# motor_module_dev.net
KiCad netlist of a schematic drawn in EAGLE
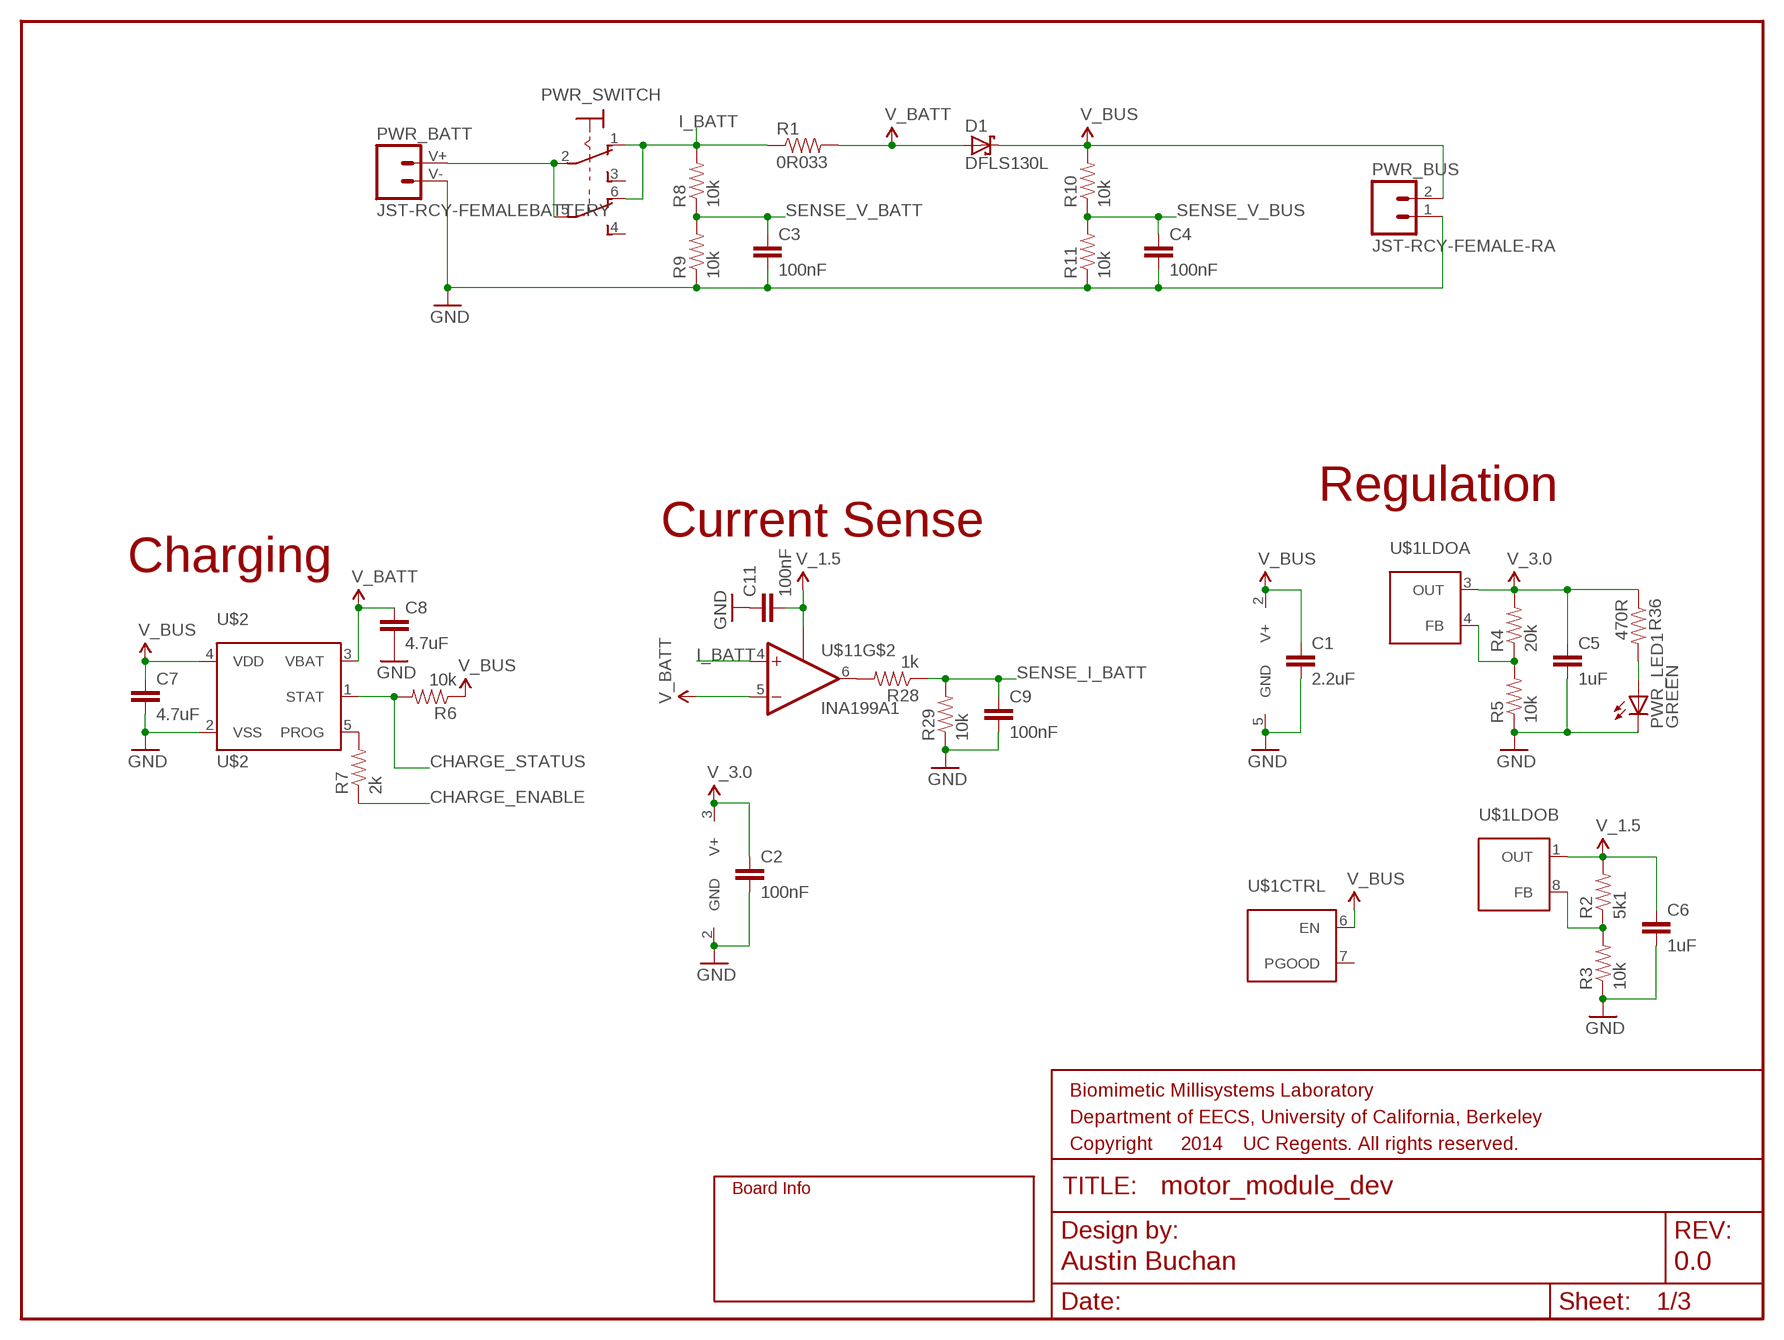
[diagram p0: schematic, sheet 1]
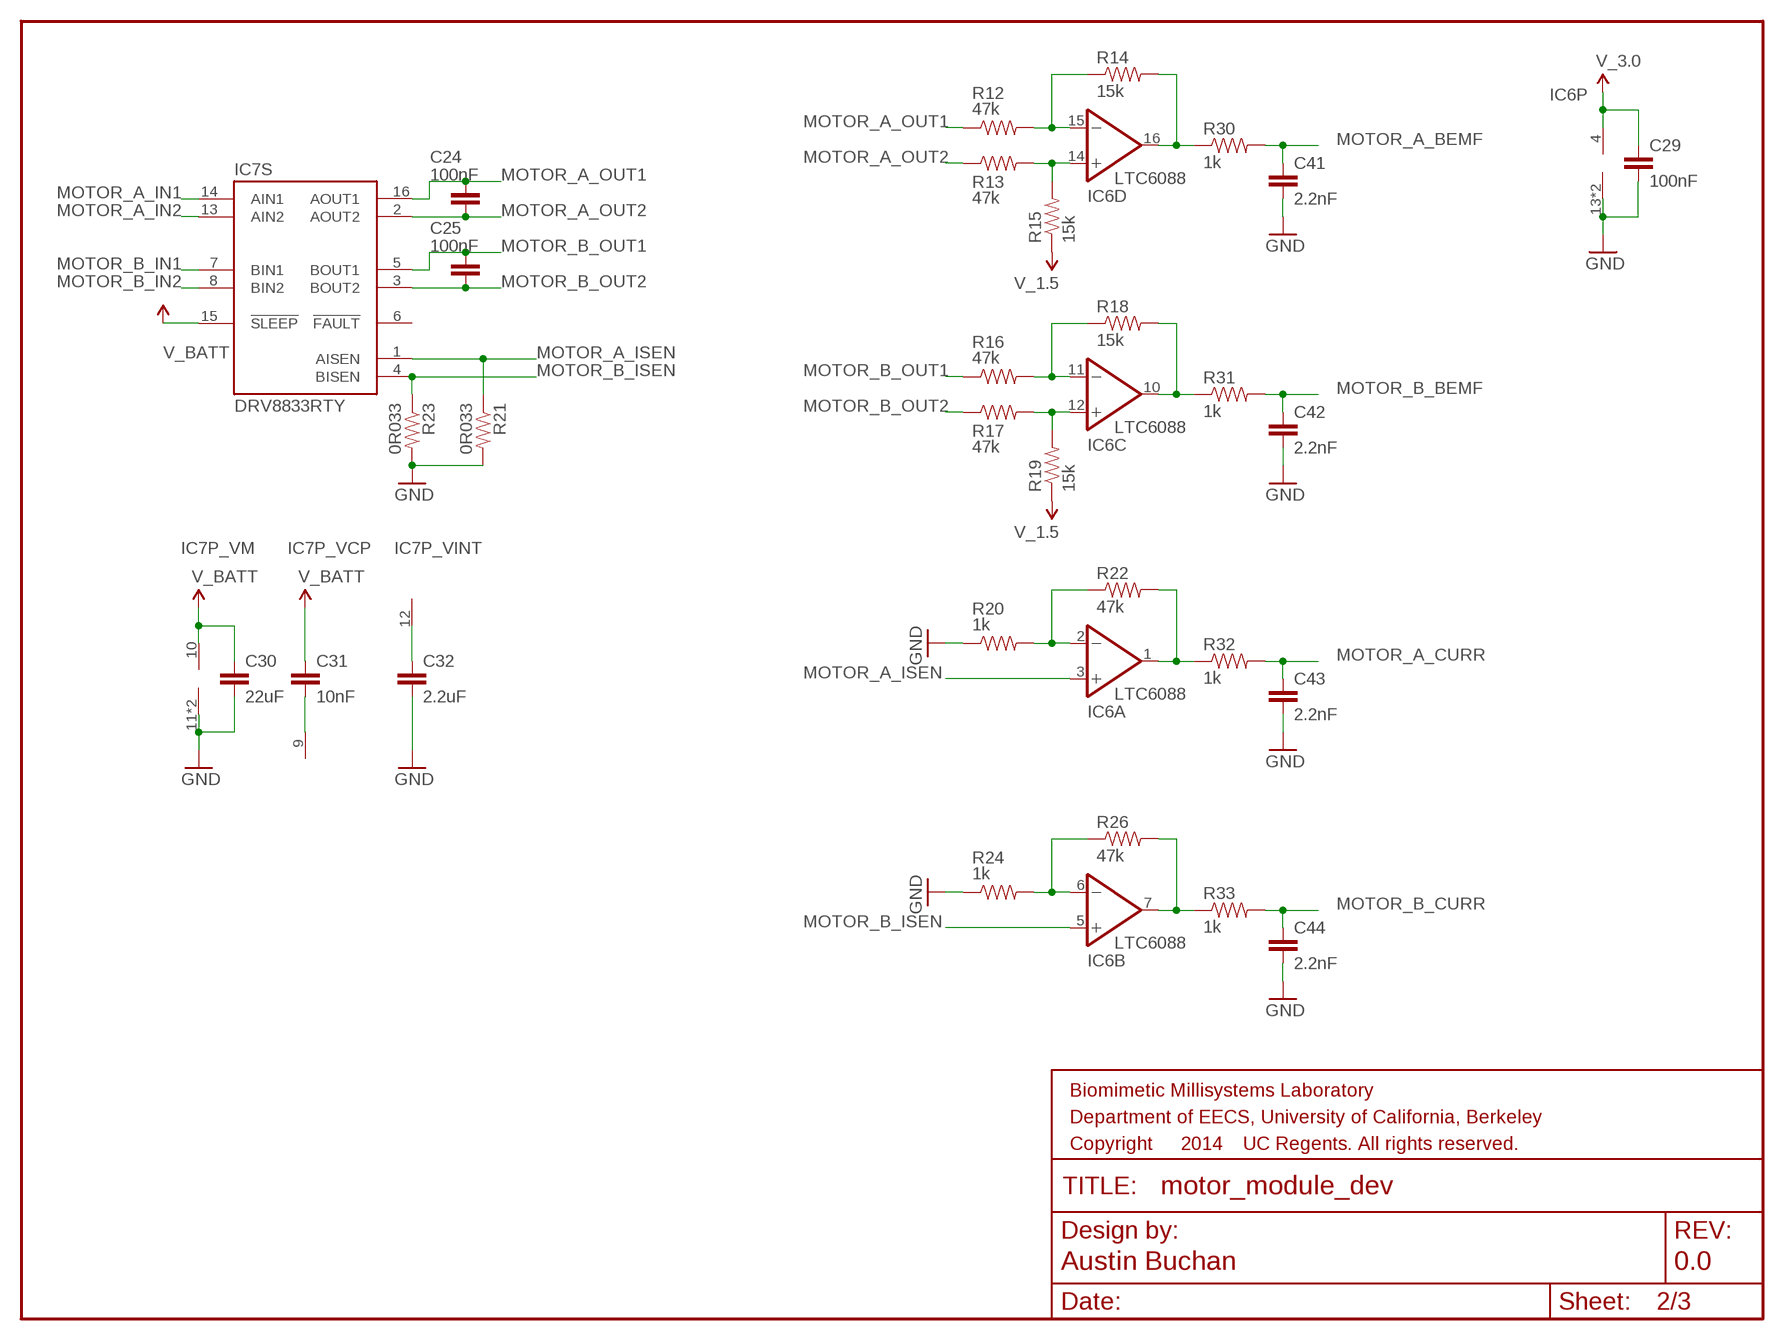
[diagram p1: schematic, sheet 2]
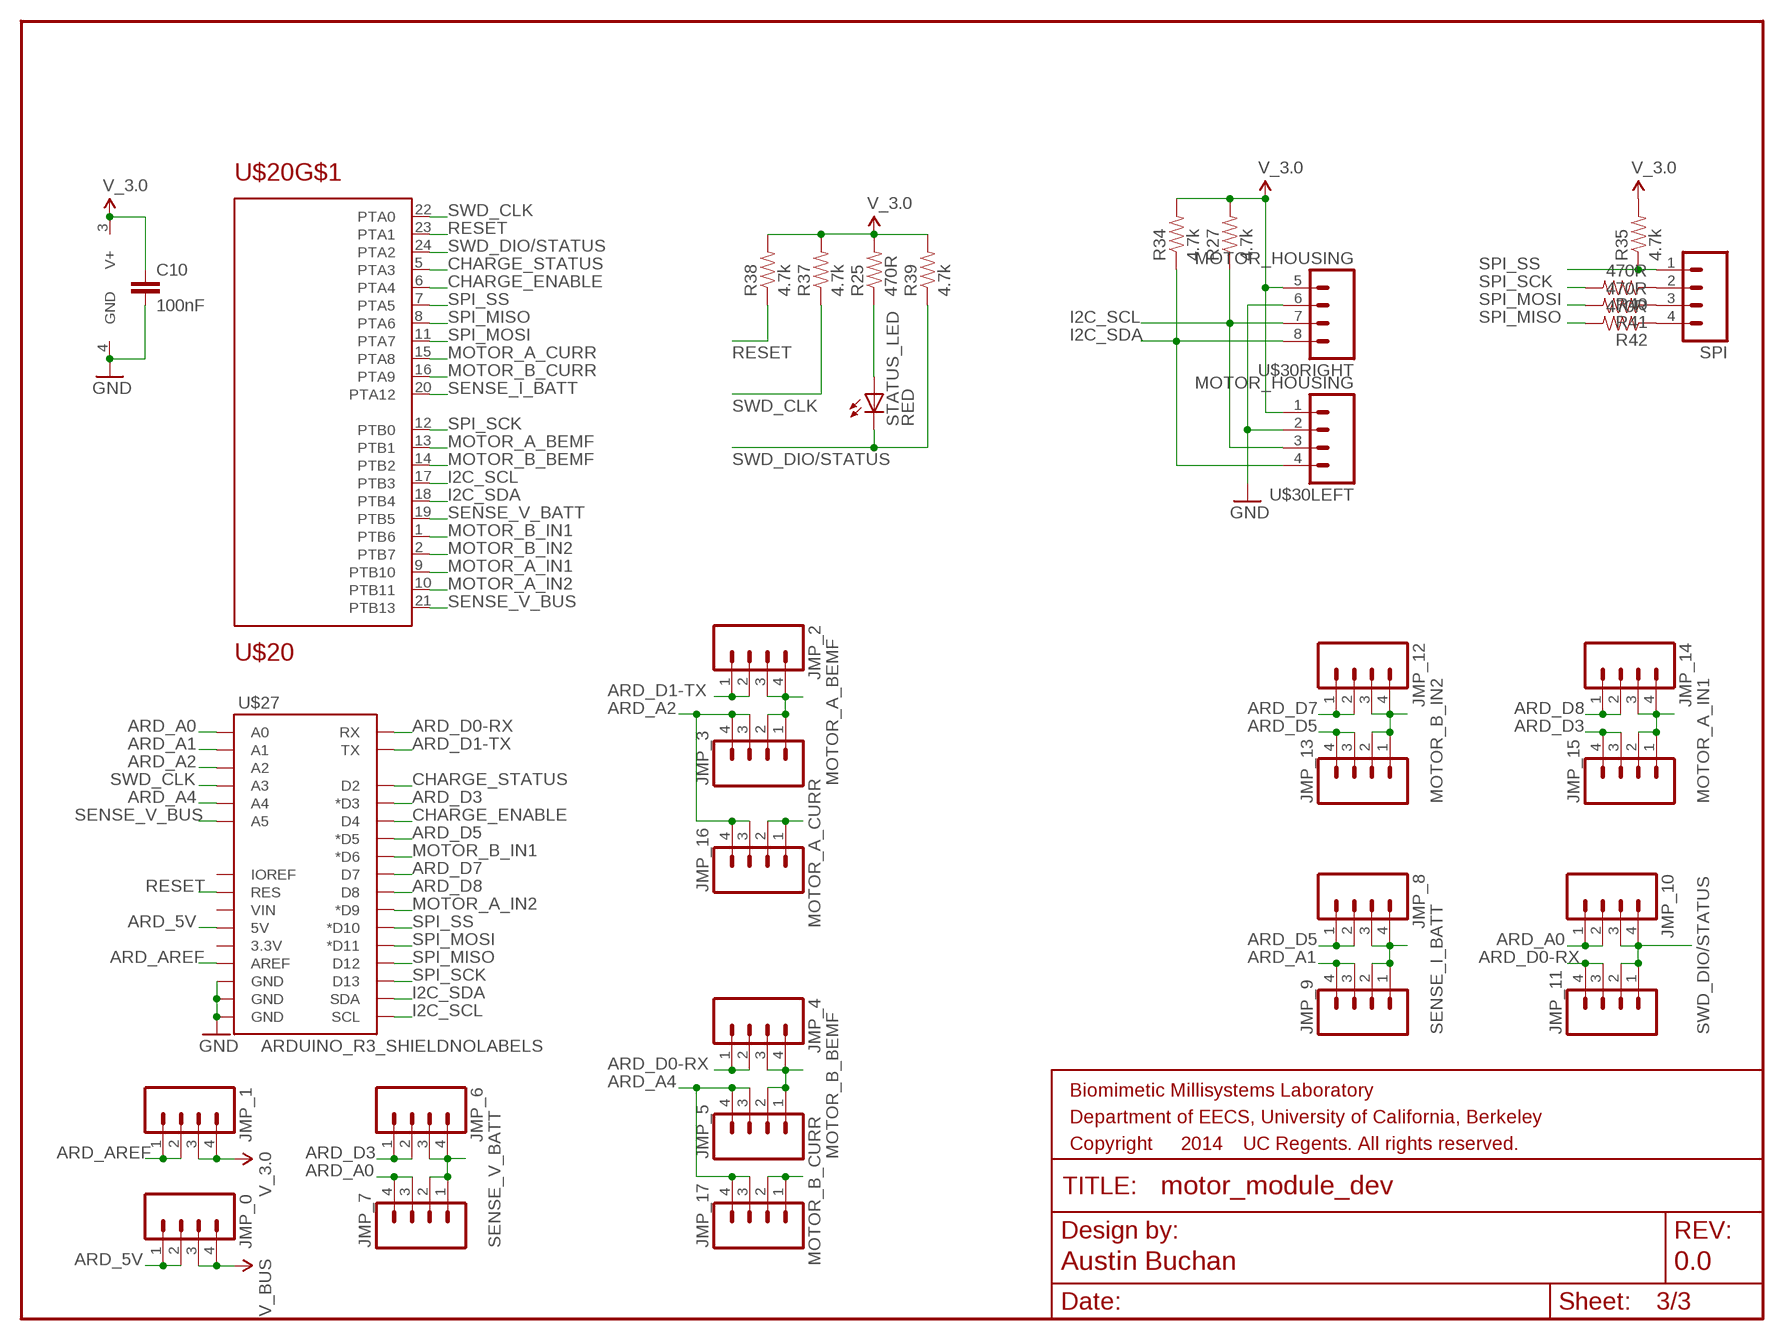
[diagram p2: schematic, sheet 3]

(export (version "E")
  (design (tool "Eeschema 10.0.6"))
  (components
    (comp (ref "C24")
      (value "100nF")
      (footprint "eagle-import:0402-CAP")
      (fields (field (name "VOLTAGE") "10V"))
      (libsource (lib "eagle-import") (part "CAP0402-CAP"))
    )
    (comp (ref "C25")
      (value "100nF")
      (footprint "eagle-import:0402-CAP")
      (fields (field (name "VOLTAGE") "10V"))
      (libsource (lib "eagle-import") (part "CAP0402-CAP"))
    )
    (comp (ref "C29")
      (value "100nF")
      (footprint "eagle-import:0402-CAP")
      (fields (field (name "VOLTAGE") "6.3V"))
      (libsource (lib "eagle-import") (part "CAP0402-CAP"))
    )
    (comp (ref "C30")
      (value "22uF")
      (footprint "eagle-import:0603-CAP")
      (fields (field (name "VOLTAGE") "10V"))
      (libsource (lib "eagle-import") (part "CAP0603-CAP"))
    )
    (comp (ref "C31")
      (value "10nF")
      (footprint "eagle-import:0402-CAP")
      (fields (field (name "VOLTAGE") "16V"))
      (libsource (lib "eagle-import") (part "CAP0402-CAP"))
    )
    (comp (ref "C32")
      (value "2.2uF")
      (footprint "eagle-import:0402-CAP")
      (fields (field (name "VOLTAGE") "6.3V"))
      (libsource (lib "eagle-import") (part "CAP0402-CAP"))
    )
    (comp (ref "C41")
      (value "2.2nF")
      (footprint "eagle-import:0402-CAP")
      (fields (field (name "VOLTAGE") "6.3V"))
      (libsource (lib "eagle-import") (part "CAP0402-CAP"))
    )
    (comp (ref "C42")
      (value "2.2nF")
      (footprint "eagle-import:0402-CAP")
      (fields (field (name "VOLTAGE") "6.3V"))
      (libsource (lib "eagle-import") (part "CAP0402-CAP"))
    )
    (comp (ref "C43")
      (value "2.2nF")
      (footprint "eagle-import:0402-CAP")
      (fields (field (name "VOLTAGE") "6.3V"))
      (libsource (lib "eagle-import") (part "CAP0402-CAP"))
    )
    (comp (ref "C44")
      (value "2.2nF")
      (footprint "eagle-import:0402-CAP")
      (fields (field (name "VOLTAGE") "6.3V"))
      (libsource (lib "eagle-import") (part "CAP0402-CAP"))
    )
    (comp (ref "IC6")
      (value "LTC6088")
      (footprint "eagle-import:DFN-16")
      (libsource (lib "eagle-import") (part "LTC6088"))
    )
    (comp (ref "IC7")
      (value "DRV8833RTY")
      (footprint "eagle-import:S-PWQFN-N16")
      (libsource (lib "eagle-import") (part "DRV8833RTY"))
    )
    (comp (ref "R12")
      (value "47k")
      (footprint "eagle-import:0402-RES")
      (fields (field (name "TOLERANCE") "1%"))
      (libsource (lib "eagle-import") (part "RESISTOR0402-RES"))
    )
    (comp (ref "R13")
      (value "47k")
      (footprint "eagle-import:0402-RES")
      (fields (field (name "TOLERANCE") "1%"))
      (libsource (lib "eagle-import") (part "RESISTOR0402-RES"))
    )
    (comp (ref "R14")
      (value "15k")
      (footprint "eagle-import:0402-RES")
      (fields (field (name "TOLERANCE") "1%"))
      (libsource (lib "eagle-import") (part "RESISTOR0402-RES"))
    )
    (comp (ref "R15")
      (value "15k")
      (footprint "eagle-import:0402-RES")
      (fields (field (name "TOLERANCE") "1%"))
      (libsource (lib "eagle-import") (part "RESISTOR0402-RES"))
    )
    (comp (ref "R16")
      (value "47k")
      (footprint "eagle-import:0402-RES")
      (fields (field (name "TOLERANCE") "1%"))
      (libsource (lib "eagle-import") (part "RESISTOR0402-RES"))
    )
    (comp (ref "R17")
      (value "47k")
      (footprint "eagle-import:0402-RES")
      (fields (field (name "TOLERANCE") "1%"))
      (libsource (lib "eagle-import") (part "RESISTOR0402-RES"))
    )
    (comp (ref "R18")
      (value "15k")
      (footprint "eagle-import:0402-RES")
      (fields (field (name "TOLERANCE") "1%"))
      (libsource (lib "eagle-import") (part "RESISTOR0402-RES"))
    )
    (comp (ref "R19")
      (value "15k")
      (footprint "eagle-import:0402-RES")
      (fields (field (name "TOLERANCE") "1%"))
      (libsource (lib "eagle-import") (part "RESISTOR0402-RES"))
    )
    (comp (ref "R20")
      (value "1k")
      (footprint "eagle-import:0402-RES")
      (fields (field (name "TOLERANCE") "1%"))
      (libsource (lib "eagle-import") (part "RESISTOR0402-RES"))
    )
    (comp (ref "R21")
      (value "0R033")
      (footprint "eagle-import:0603-RES")
      (libsource (lib "eagle-import") (part "RESISTOR0603-RES"))
    )
    (comp (ref "R22")
      (value "47k")
      (footprint "eagle-import:0402-RES")
      (fields (field (name "TOLERANCE") "1%"))
      (libsource (lib "eagle-import") (part "RESISTOR0402-RES"))
    )
    (comp (ref "R23")
      (value "0R033")
      (footprint "eagle-import:0603-RES")
      (libsource (lib "eagle-import") (part "RESISTOR0603-RES"))
    )
    (comp (ref "R24")
      (value "1k")
      (footprint "eagle-import:0402-RES")
      (fields (field (name "TOLERANCE") "1%"))
      (libsource (lib "eagle-import") (part "RESISTOR0402-RES"))
    )
    (comp (ref "R26")
      (value "47k")
      (footprint "eagle-import:0402-RES")
      (fields (field (name "TOLERANCE") "1%"))
      (libsource (lib "eagle-import") (part "RESISTOR0402-RES"))
    )
    (comp (ref "R30")
      (value "1k")
      (footprint "eagle-import:0402-RES")
      (libsource (lib "eagle-import") (part "RESISTOR0402-RES"))
    )
    (comp (ref "R31")
      (value "1k")
      (footprint "eagle-import:0402-RES")
      (libsource (lib "eagle-import") (part "RESISTOR0402-RES"))
    )
    (comp (ref "R32")
      (value "1k")
      (footprint "eagle-import:0402-RES")
      (libsource (lib "eagle-import") (part "RESISTOR0402-RES"))
    )
    (comp (ref "R33")
      (value "1k")
      (footprint "eagle-import:0402-RES")
      (libsource (lib "eagle-import") (part "RESISTOR0402-RES"))
    )
    (comp (ref "C1")
      (value "2.2uF")
      (footprint "eagle-import:0402-CAP")
      (fields (field (name "VOLTAGE") "10V"))
      (libsource (lib "eagle-import") (part "CAP0402-CAP"))
    )
    (comp (ref "C2")
      (value "100nF")
      (footprint "eagle-import:0402-CAP")
      (fields (field (name "VOLTAGE") "6.3V"))
      (libsource (lib "eagle-import") (part "CAP0402-CAP"))
    )
    (comp (ref "C3")
      (value "100nF")
      (footprint "eagle-import:0402-CAP")
      (fields (field (name "VOLTAGE") "6.3V"))
      (libsource (lib "eagle-import") (part "CAP0402-CAP"))
    )
    (comp (ref "C4")
      (value "100nF")
      (footprint "eagle-import:0402-CAP")
      (fields (field (name "VOLTAGE") "6.3V"))
      (libsource (lib "eagle-import") (part "CAP0402-CAP"))
    )
    (comp (ref "C5")
      (value "1uF")
      (footprint "eagle-import:0402-CAP")
      (fields (field (name "VOLTAGE") "6.3V"))
      (libsource (lib "eagle-import") (part "CAP0402-CAP"))
    )
    (comp (ref "C6")
      (value "1uF")
      (footprint "eagle-import:0402-CAP")
      (fields (field (name "VOLTAGE") "6.3V"))
      (libsource (lib "eagle-import") (part "CAP0402-CAP"))
    )
    (comp (ref "C7")
      (value "4.7uF")
      (footprint "eagle-import:0402-CAP")
      (fields (field (name "VOLTAGE") "10V"))
      (libsource (lib "eagle-import") (part "CAP0402-CAP"))
    )
    (comp (ref "C8")
      (value "4.7uF")
      (footprint "eagle-import:0402-CAP")
      (fields (field (name "VOLTAGE") "10V"))
      (libsource (lib "eagle-import") (part "CAP0402-CAP"))
    )
    (comp (ref "C9")
      (value "100nF")
      (footprint "eagle-import:0402-CAP")
      (fields (field (name "VOLTAGE") "6.3V"))
      (libsource (lib "eagle-import") (part "CAP0402-CAP"))
    )
    (comp (ref "C11")
      (value "100nF")
      (footprint "eagle-import:0402-CAP")
      (fields (field (name "VOLTAGE") "6.3V"))
      (libsource (lib "eagle-import") (part "CAP0402-CAP"))
    )
    (comp (ref "D1")
      (value "DFLS130L")
      (footprint "eagle-import:POWERDI123")
      (libsource (lib "eagle-import") (part "DFLS130L"))
    )
    (comp (ref "PWR_BATT")
      (value "JST-RCY-FEMALEBATTERY")
      (footprint "eagle-import:TP_LIPO_160MAH")
      (libsource (lib "eagle-import") (part "JST-RCY-FEMALEBATTERY"))
    )
    (comp (ref "PWR_BUS")
      (value "JST-RCY-FEMALE-RA")
      (footprint "eagle-import:JST_2_FEMALE")
      (libsource (lib "eagle-import") (part "JST-RCY-FEMALE-RA"))
    )
    (comp (ref "PWR_LED1")
      (value "GREEN")
      (footprint "eagle-import:LED-0603")
      (libsource (lib "eagle-import") (part "LED0603"))
    )
    (comp (ref "PWR_SWITCH")
      (value "JS202011SCQN")
      (footprint "eagle-import:JS202011SCQN")
      (libsource (lib "eagle-import") (part "JS202011SCQN"))
    )
    (comp (ref "R1")
      (value "0R033")
      (footprint "eagle-import:0603-RES")
      (libsource (lib "eagle-import") (part "RESISTOR0603-RES"))
    )
    (comp (ref "R2")
      (value "5k1")
      (footprint "eagle-import:0402-RES")
      (libsource (lib "eagle-import") (part "RESISTOR0402-RES"))
    )
    (comp (ref "R3")
      (value "10k")
      (footprint "eagle-import:0402-RES")
      (libsource (lib "eagle-import") (part "RESISTOR0402-RES"))
    )
    (comp (ref "R4")
      (value "20k")
      (footprint "eagle-import:0402-RES")
      (libsource (lib "eagle-import") (part "RESISTOR0402-RES"))
    )
    (comp (ref "R5")
      (value "10k")
      (footprint "eagle-import:0402-RES")
      (libsource (lib "eagle-import") (part "RESISTOR0402-RES"))
    )
    (comp (ref "R6")
      (value "10k")
      (footprint "eagle-import:0402-RES")
      (libsource (lib "eagle-import") (part "RESISTOR0402-RES"))
    )
    (comp (ref "R7")
      (value "2k")
      (footprint "eagle-import:0402-RES")
      (libsource (lib "eagle-import") (part "RESISTOR0402-RES"))
    )
    (comp (ref "R8")
      (value "10k")
      (footprint "eagle-import:0402-RES")
      (libsource (lib "eagle-import") (part "RESISTOR0402-RES"))
    )
    (comp (ref "R9")
      (value "10k")
      (footprint "eagle-import:0402-RES")
      (libsource (lib "eagle-import") (part "RESISTOR0402-RES"))
    )
    (comp (ref "R10")
      (value "10k")
      (footprint "eagle-import:0402-RES")
      (libsource (lib "eagle-import") (part "RESISTOR0402-RES"))
    )
    (comp (ref "R11")
      (value "10k")
      (footprint "eagle-import:0402-RES")
      (libsource (lib "eagle-import") (part "RESISTOR0402-RES"))
    )
    (comp (ref "R28")
      (value "1k")
      (footprint "eagle-import:0402-RES")
      (libsource (lib "eagle-import") (part "RESISTOR0402-RES"))
    )
    (comp (ref "R29")
      (value "10k")
      (footprint "eagle-import:0402-RES")
      (libsource (lib "eagle-import") (part "RESISTOR0402-RES"))
    )
    (comp (ref "R36")
      (value "470R")
      (footprint "eagle-import:0402-RES")
      (libsource (lib "eagle-import") (part "RESISTOR0402-RES"))
    )
    (comp (ref "U$1")
      (value "SC560C")
      (footprint "eagle-import:MLPQ-UT8")
      (libsource (lib "eagle-import") (part "SC560C"))
    )
    (comp (ref "U$2")
      (value "MCP73831T")
      (footprint "eagle-import:SOT23-5")
      (libsource (lib "eagle-import") (part "MCP73831T"))
    )
    (comp (ref "U$11")
      (value "INA199A1")
      (footprint "eagle-import:SC70-6")
      (libsource (lib "eagle-import") (part "INA199A1"))
    )
    (comp (ref "U$31")
      (value "INFO")
      (footprint "eagle-import:INFO")
      (fields
        (field (name "AUTHOR") "Austin Buchan")
        (field (name "DATE") "Feb. 2014")
        (field (name "DESIGN") "Motor Control Dev")
        (field (name "ORGANIZATION") "UC Berkeley Biomimetic Millisystems Lab")
        (field (name "REVISION") "r0.1")
      )
      (libsource (lib "eagle-import") (part "INFO"))
    )
    (comp (ref "C10")
      (value "100nF")
      (footprint "eagle-import:0402-CAP")
      (fields (field (name "VOLTAGE") "6.3V"))
      (libsource (lib "eagle-import") (part "CAP0402-CAP"))
    )
    (comp (ref "JMP_0")
      (value "M041X04_NO_SILK")
      (footprint "eagle-import:1X04_NO_SILK")
      (libsource (lib "eagle-import") (part "M041X04_NO_SILK"))
    )
    (comp (ref "JMP_1")
      (value "M041X04_NO_SILK")
      (footprint "eagle-import:1X04_NO_SILK")
      (libsource (lib "eagle-import") (part "M041X04_NO_SILK"))
    )
    (comp (ref "JMP_2")
      (value "M041X04_NO_SILK")
      (footprint "eagle-import:1X04_NO_SILK")
      (libsource (lib "eagle-import") (part "M041X04_NO_SILK"))
    )
    (comp (ref "JMP_3")
      (value "M041X04_NO_SILK")
      (footprint "eagle-import:1X04_NO_SILK")
      (libsource (lib "eagle-import") (part "M041X04_NO_SILK"))
    )
    (comp (ref "JMP_4")
      (value "M041X04_NO_SILK")
      (footprint "eagle-import:1X04_NO_SILK")
      (libsource (lib "eagle-import") (part "M041X04_NO_SILK"))
    )
    (comp (ref "JMP_5")
      (value "M041X04_NO_SILK")
      (footprint "eagle-import:1X04_NO_SILK")
      (libsource (lib "eagle-import") (part "M041X04_NO_SILK"))
    )
    (comp (ref "JMP_6")
      (value "M041X04_NO_SILK")
      (footprint "eagle-import:1X04_NO_SILK")
      (libsource (lib "eagle-import") (part "M041X04_NO_SILK"))
    )
    (comp (ref "JMP_7")
      (value "M041X04_NO_SILK")
      (footprint "eagle-import:1X04_NO_SILK")
      (libsource (lib "eagle-import") (part "M041X04_NO_SILK"))
    )
    (comp (ref "JMP_8")
      (value "M041X04_NO_SILK")
      (footprint "eagle-import:1X04_NO_SILK")
      (libsource (lib "eagle-import") (part "M041X04_NO_SILK"))
    )
    (comp (ref "JMP_9")
      (value "M041X04_NO_SILK")
      (footprint "eagle-import:1X04_NO_SILK")
      (libsource (lib "eagle-import") (part "M041X04_NO_SILK"))
    )
    (comp (ref "JMP_10")
      (value "M041X04_NO_SILK")
      (footprint "eagle-import:1X04_NO_SILK")
      (libsource (lib "eagle-import") (part "M041X04_NO_SILK"))
    )
    (comp (ref "JMP_11")
      (value "M041X04_NO_SILK")
      (footprint "eagle-import:1X04_NO_SILK")
      (libsource (lib "eagle-import") (part "M041X04_NO_SILK"))
    )
    (comp (ref "JMP_12")
      (value "M041X04_NO_SILK")
      (footprint "eagle-import:1X04_NO_SILK")
      (libsource (lib "eagle-import") (part "M041X04_NO_SILK"))
    )
    (comp (ref "JMP_13")
      (value "M041X04_NO_SILK")
      (footprint "eagle-import:1X04_NO_SILK")
      (libsource (lib "eagle-import") (part "M041X04_NO_SILK"))
    )
    (comp (ref "JMP_14")
      (value "M041X04_NO_SILK")
      (footprint "eagle-import:1X04_NO_SILK")
      (libsource (lib "eagle-import") (part "M041X04_NO_SILK"))
    )
    (comp (ref "JMP_15")
      (value "M041X04_NO_SILK")
      (footprint "eagle-import:1X04_NO_SILK")
      (libsource (lib "eagle-import") (part "M041X04_NO_SILK"))
    )
    (comp (ref "JMP_16")
      (value "M041X04_NO_SILK")
      (footprint "eagle-import:1X04_NO_SILK")
      (libsource (lib "eagle-import") (part "M041X04_NO_SILK"))
    )
    (comp (ref "JMP_17")
      (value "M041X04_NO_SILK")
      (footprint "eagle-import:1X04_NO_SILK")
      (libsource (lib "eagle-import") (part "M041X04_NO_SILK"))
    )
    (comp (ref "R25")
      (value "470R")
      (footprint "eagle-import:0402-RES")
      (libsource (lib "eagle-import") (part "RESISTOR0402-RES"))
    )
    (comp (ref "R27")
      (value "4.7k")
      (footprint "eagle-import:0402-RES")
      (libsource (lib "eagle-import") (part "RESISTOR0402-RES"))
    )
    (comp (ref "R34")
      (value "4.7k")
      (footprint "eagle-import:0402-RES")
      (libsource (lib "eagle-import") (part "RESISTOR0402-RES"))
    )
    (comp (ref "R35")
      (value "4.7k")
      (footprint "eagle-import:0402-RES")
      (libsource (lib "eagle-import") (part "RESISTOR0402-RES"))
    )
    (comp (ref "R37")
      (value "4.7k")
      (footprint "eagle-import:0402-RES")
      (libsource (lib "eagle-import") (part "RESISTOR0402-RES"))
    )
    (comp (ref "R38")
      (value "4.7k")
      (footprint "eagle-import:0402-RES")
      (libsource (lib "eagle-import") (part "RESISTOR0402-RES"))
    )
    (comp (ref "R39")
      (value "4.7k")
      (footprint "eagle-import:0402-RES")
      (libsource (lib "eagle-import") (part "RESISTOR0402-RES"))
    )
    (comp (ref "R40")
      (value "470R")
      (footprint "eagle-import:0402-RES")
      (libsource (lib "eagle-import") (part "RESISTOR0402-RES"))
    )
    (comp (ref "R41")
      (value "470R")
      (footprint "eagle-import:0402-RES")
      (libsource (lib "eagle-import") (part "RESISTOR0402-RES"))
    )
    (comp (ref "R42")
      (value "470R")
      (footprint "eagle-import:0402-RES")
      (libsource (lib "eagle-import") (part "RESISTOR0402-RES"))
    )
    (comp (ref "SPI")
      (value "M041X04_NO_SILK")
      (footprint "eagle-import:1X04_NO_SILK")
      (libsource (lib "eagle-import") (part "M041X04_NO_SILK"))
    )
    (comp (ref "STATUS_LED")
      (value "RED")
      (footprint "eagle-import:LED-0603")
      (libsource (lib "eagle-import") (part "LED0603"))
    )
    (comp (ref "U$20")
      (value "MKL05Z32VFK4")
      (footprint "eagle-import:QFN-24")
      (libsource (lib "eagle-import") (part "MKL05Z32VFK4"))
    )
    (comp (ref "U$27")
      (value "ARDUINO_R3_SHIELDNOLABELS")
      (footprint "eagle-import:UNO_R3_SHIELD_NOLABELS")
      (libsource (lib "eagle-import") (part "ARDUINO_R3_SHIELDNOLABELS"))
    )
    (comp (ref "U$30")
      (value "MOTOR_HOUSING")
      (footprint "eagle-import:MOTOR_HOUSING")
      (libsource (lib "eagle-import") (part "MOTOR_HOUSING"))
    )
  )
  (nets
    (net (code "1") (name "ARD_5V") (class "Default")
      (node (ref "JMP_0") (pin "1") (pinfunction "1_1") (pintype "passive"))
      (node (ref "JMP_0") (pin "2") (pinfunction "2_2") (pintype "passive"))
      (node (ref "U$27") (pin "5V") (pinfunction "5V_5V") (pintype "bidirectional"))
    )
    (net (code "2") (name "ARD_A0") (class "Default")
      (node (ref "JMP_10") (pin "1") (pinfunction "1_1") (pintype "passive"))
      (node (ref "JMP_10") (pin "2") (pinfunction "2_2") (pintype "passive"))
      (node (ref "JMP_7") (pin "3") (pinfunction "3_3") (pintype "passive"))
      (node (ref "JMP_7") (pin "4") (pinfunction "4_4") (pintype "passive"))
      (node (ref "U$27") (pin "A0") (pinfunction "A0_A0") (pintype "bidirectional"))
    )
    (net (code "3") (name "ARD_A1") (class "Default")
      (node (ref "JMP_9") (pin "3") (pinfunction "3_3") (pintype "passive"))
      (node (ref "JMP_9") (pin "4") (pinfunction "4_4") (pintype "passive"))
      (node (ref "U$27") (pin "A1") (pinfunction "A1_A1") (pintype "bidirectional"))
    )
    (net (code "4") (name "ARD_A2") (class "Default")
      (node (ref "JMP_16") (pin "3") (pinfunction "3_3") (pintype "passive"))
      (node (ref "JMP_16") (pin "4") (pinfunction "4_4") (pintype "passive"))
      (node (ref "JMP_3") (pin "3") (pinfunction "3_3") (pintype "passive"))
      (node (ref "JMP_3") (pin "4") (pinfunction "4_4") (pintype "passive"))
      (node (ref "U$27") (pin "A2") (pinfunction "A2_A2") (pintype "bidirectional"))
    )
    (net (code "5") (name "ARD_A4") (class "Default")
      (node (ref "JMP_17") (pin "3") (pinfunction "3_3") (pintype "passive"))
      (node (ref "JMP_17") (pin "4") (pinfunction "4_4") (pintype "passive"))
      (node (ref "JMP_5") (pin "3") (pinfunction "3_3") (pintype "passive"))
      (node (ref "JMP_5") (pin "4") (pinfunction "4_4") (pintype "passive"))
      (node (ref "U$27") (pin "A4") (pinfunction "A4_A4") (pintype "bidirectional"))
    )
    (net (code "6") (name "ARD_AREF") (class "Default")
      (node (ref "JMP_1") (pin "1") (pinfunction "1_1") (pintype "passive"))
      (node (ref "JMP_1") (pin "2") (pinfunction "2_2") (pintype "passive"))
      (node (ref "U$27") (pin "AREF") (pinfunction "AREF_AREF") (pintype "bidirectional"))
    )
    (net (code "7") (name "ARD_D0-RX") (class "Default")
      (node (ref "JMP_11") (pin "3") (pinfunction "3_3") (pintype "passive"))
      (node (ref "JMP_11") (pin "4") (pinfunction "4_4") (pintype "passive"))
      (node (ref "JMP_4") (pin "1") (pinfunction "1_1") (pintype "passive"))
      (node (ref "JMP_4") (pin "2") (pinfunction "2_2") (pintype "passive"))
      (node (ref "U$27") (pin "RX") (pinfunction "RX_RX") (pintype "bidirectional"))
    )
    (net (code "8") (name "ARD_D1-TX") (class "Default")
      (node (ref "JMP_2") (pin "1") (pinfunction "1_1") (pintype "passive"))
      (node (ref "JMP_2") (pin "2") (pinfunction "2_2") (pintype "passive"))
      (node (ref "U$27") (pin "TX") (pinfunction "TX_TX") (pintype "bidirectional"))
    )
    (net (code "9") (name "ARD_D3") (class "Default")
      (node (ref "JMP_15") (pin "3") (pinfunction "3_3") (pintype "passive"))
      (node (ref "JMP_15") (pin "4") (pinfunction "4_4") (pintype "passive"))
      (node (ref "JMP_6") (pin "1") (pinfunction "1_1") (pintype "passive"))
      (node (ref "JMP_6") (pin "2") (pinfunction "2_2") (pintype "passive"))
      (node (ref "U$27") (pin "D3") (pinfunction "*D3_D3") (pintype "bidirectional"))
    )
    (net (code "10") (name "ARD_D5") (class "Default")
      (node (ref "JMP_13") (pin "3") (pinfunction "3_3") (pintype "passive"))
      (node (ref "JMP_13") (pin "4") (pinfunction "4_4") (pintype "passive"))
      (node (ref "JMP_8") (pin "1") (pinfunction "1_1") (pintype "passive"))
      (node (ref "JMP_8") (pin "2") (pinfunction "2_2") (pintype "passive"))
      (node (ref "U$27") (pin "D5") (pinfunction "*D5_D5") (pintype "bidirectional"))
    )
    (net (code "11") (name "ARD_D7") (class "Default")
      (node (ref "JMP_12") (pin "1") (pinfunction "1_1") (pintype "passive"))
      (node (ref "JMP_12") (pin "2") (pinfunction "2_2") (pintype "passive"))
      (node (ref "U$27") (pin "D7") (pinfunction "D7_D7") (pintype "bidirectional"))
    )
    (net (code "12") (name "ARD_D8") (class "Default")
      (node (ref "JMP_14") (pin "1") (pinfunction "1_1") (pintype "passive"))
      (node (ref "JMP_14") (pin "2") (pinfunction "2_2") (pintype "passive"))
      (node (ref "U$27") (pin "D8") (pinfunction "D8_D8") (pintype "bidirectional"))
    )
    (net (code "13") (name "CHARGE_ENABLE") (class "Default")
      (node (ref "R7") (pin "1") (pinfunction "1_1") (pintype "passive"))
      (node (ref "U$20") (pin "6") (pinfunction "PTA4_6") (pintype "bidirectional"))
      (node (ref "U$27") (pin "D4") (pinfunction "D4_D4") (pintype "bidirectional"))
    )
    (net (code "14") (name "CHARGE_STATUS") (class "Default")
      (node (ref "R6") (pin "2") (pinfunction "2_2") (pintype "passive"))
      (node (ref "U$2") (pin "1") (pinfunction "STAT_1") (pintype "bidirectional"))
      (node (ref "U$20") (pin "5") (pinfunction "PTA3_5") (pintype "bidirectional"))
      (node (ref "U$27") (pin "D2") (pinfunction "D2_D2") (pintype "bidirectional"))
    )
    (net (code "15") (name "GND") (class "Default")
      (node (ref "C1") (pin "2") (pinfunction "2_2") (pintype "passive"))
      (node (ref "C10") (pin "2") (pinfunction "2_2") (pintype "passive"))
      (node (ref "C11") (pin "1") (pinfunction "1_1") (pintype "passive"))
      (node (ref "C2") (pin "2") (pinfunction "2_2") (pintype "passive"))
      (node (ref "C29") (pin "2") (pinfunction "2_2") (pintype "passive"))
      (node (ref "C3") (pin "2") (pinfunction "2_2") (pintype "passive"))
      (node (ref "C30") (pin "2") (pinfunction "2_2") (pintype "passive"))
      (node (ref "C32") (pin "2") (pinfunction "2_2") (pintype "passive"))
      (node (ref "C4") (pin "2") (pinfunction "2_2") (pintype "passive"))
      (node (ref "C41") (pin "2") (pinfunction "2_2") (pintype "passive"))
      (node (ref "C42") (pin "2") (pinfunction "2_2") (pintype "passive"))
      (node (ref "C43") (pin "2") (pinfunction "2_2") (pintype "passive"))
      (node (ref "C44") (pin "2") (pinfunction "2_2") (pintype "passive"))
      (node (ref "C5") (pin "2") (pinfunction "2_2") (pintype "passive"))
      (node (ref "C6") (pin "2") (pinfunction "2_2") (pintype "passive"))
      (node (ref "C7") (pin "2") (pinfunction "2_2") (pintype "passive"))
      (node (ref "C8") (pin "2") (pinfunction "2_2") (pintype "passive"))
      (node (ref "C9") (pin "2") (pinfunction "2_2") (pintype "passive"))
      (node (ref "IC6") (pin "13") (pinfunction "V-_13") (pintype "power_in"))
      (node (ref "IC6") (pin "PAD") (pinfunction "V-_PAD") (pintype "power_in"))
      (node (ref "IC7") (pin "11") (pinfunction "V-_11") (pintype "power_in"))
      (node (ref "IC7") (pin "PPAD") (pinfunction "V-_PPAD") (pintype "power_in"))
      (node (ref "PWR_BATT") (pin "V-") (pinfunction "1_V-") (pintype "passive"))
      (node (ref "PWR_BUS") (pin "1") (pinfunction "1_1") (pintype "passive"))
      (node (ref "PWR_LED1") (pin "C") (pinfunction "C_C") (pintype "passive"))
      (node (ref "R11") (pin "1") (pinfunction "1_1") (pintype "passive"))
      (node (ref "R20") (pin "1") (pinfunction "1_1") (pintype "passive"))
      (node (ref "R21") (pin "2") (pinfunction "2_2") (pintype "passive"))
      (node (ref "R23") (pin "2") (pinfunction "2_2") (pintype "passive"))
      (node (ref "R24") (pin "1") (pinfunction "1_1") (pintype "passive"))
      (node (ref "R29") (pin "1") (pinfunction "1_1") (pintype "passive"))
      (node (ref "R3") (pin "1") (pinfunction "1_1") (pintype "passive"))
      (node (ref "R5") (pin "1") (pinfunction "1_1") (pintype "passive"))
      (node (ref "R9") (pin "1") (pinfunction "1_1") (pintype "passive"))
      (node (ref "U$1") (pin "5") (pinfunction "GND_5") (pintype "power_in"))
      (node (ref "U$11") (pin "2") (pinfunction "GND_2") (pintype "power_in"))
      (node (ref "U$2") (pin "2") (pinfunction "VSS_2") (pintype "bidirectional"))
      (node (ref "U$20") (pin "4") (pinfunction "GND_4") (pintype "power_in"))
      (node (ref "U$27") (pin "GND@0") (pinfunction "GND_GND@0") (pintype "bidirectional"))
      (node (ref "U$27") (pin "GND@1") (pinfunction "GND_GND@1") (pintype "bidirectional"))
      (node (ref "U$27") (pin "GND@2") (pinfunction "GND_GND@2") (pintype "bidirectional"))
      (node (ref "U$30") (pin "2") (pinfunction "2_2") (pintype "passive"))
      (node (ref "U$30") (pin "6") (pinfunction "2_6") (pintype "passive"))
    )
    (net (code "16") (name "I2C_SCL") (class "Default")
      (node (ref "R27") (pin "1") (pinfunction "1_1") (pintype "passive"))
      (node (ref "U$20") (pin "17") (pinfunction "PTB3_17") (pintype "bidirectional"))
      (node (ref "U$27") (pin "SCL") (pinfunction "SCL_SCL") (pintype "bidirectional"))
      (node (ref "U$30") (pin "3") (pinfunction "3_3") (pintype "passive"))
      (node (ref "U$30") (pin "7") (pinfunction "3_7") (pintype "passive"))
    )
    (net (code "17") (name "I2C_SDA") (class "Default")
      (node (ref "R34") (pin "1") (pinfunction "1_1") (pintype "passive"))
      (node (ref "U$20") (pin "18") (pinfunction "PTB4_18") (pintype "bidirectional"))
      (node (ref "U$27") (pin "SDA") (pinfunction "SDA_SDA") (pintype "bidirectional"))
      (node (ref "U$30") (pin "4") (pinfunction "4_4") (pintype "passive"))
      (node (ref "U$30") (pin "8") (pinfunction "4_8") (pintype "passive"))
    )
    (net (code "18") (name "I_BATT") (class "Default")
      (node (ref "PWR_SWITCH") (pin "1") (pinfunction "O_1") (pintype "passive"))
      (node (ref "PWR_SWITCH") (pin "6") (pinfunction "O_6") (pintype "passive"))
      (node (ref "R1") (pin "1") (pinfunction "1_1") (pintype "passive"))
      (node (ref "R8") (pin "2") (pinfunction "2_2") (pintype "passive"))
      (node (ref "U$11") (pin "4") (pinfunction "+IN_4") (pintype "input"))
    )
    (net (code "19") (name "MOTOR_A_BEMF") (class "Default")
      (node (ref "C41") (pin "1") (pinfunction "1_1") (pintype "passive"))
      (node (ref "JMP_2") (pin "3") (pinfunction "3_3") (pintype "passive"))
      (node (ref "JMP_2") (pin "4") (pinfunction "4_4") (pintype "passive"))
      (node (ref "JMP_3") (pin "1") (pinfunction "1_1") (pintype "passive"))
      (node (ref "JMP_3") (pin "2") (pinfunction "2_2") (pintype "passive"))
      (node (ref "R30") (pin "2") (pinfunction "2_2") (pintype "passive"))
      (node (ref "U$20") (pin "13") (pinfunction "PTB1_13") (pintype "bidirectional"))
    )
    (net (code "20") (name "MOTOR_A_CURR") (class "Default")
      (node (ref "C43") (pin "1") (pinfunction "1_1") (pintype "passive"))
      (node (ref "JMP_16") (pin "1") (pinfunction "1_1") (pintype "passive"))
      (node (ref "JMP_16") (pin "2") (pinfunction "2_2") (pintype "passive"))
      (node (ref "R32") (pin "2") (pinfunction "2_2") (pintype "passive"))
      (node (ref "U$20") (pin "15") (pinfunction "PTA8_15") (pintype "bidirectional"))
    )
    (net (code "21") (name "MOTOR_A_IN1") (class "Default")
      (node (ref "IC7") (pin "14") (pinfunction "AIN1_14") (pintype "bidirectional"))
      (node (ref "JMP_14") (pin "3") (pinfunction "3_3") (pintype "passive"))
      (node (ref "JMP_14") (pin "4") (pinfunction "4_4") (pintype "passive"))
      (node (ref "JMP_15") (pin "1") (pinfunction "1_1") (pintype "passive"))
      (node (ref "JMP_15") (pin "2") (pinfunction "2_2") (pintype "passive"))
      (node (ref "U$20") (pin "9") (pinfunction "PTB10_9") (pintype "bidirectional"))
    )
    (net (code "22") (name "MOTOR_A_IN2") (class "Default")
      (node (ref "IC7") (pin "13") (pinfunction "AIN2_13") (pintype "bidirectional"))
      (node (ref "U$20") (pin "10") (pinfunction "PTB11_10") (pintype "bidirectional"))
      (node (ref "U$27") (pin "D9") (pinfunction "*D9_D9") (pintype "bidirectional"))
    )
    (net (code "23") (name "MOTOR_A_ISEN") (class "Default")
      (node (ref "IC6") (pin "3") (pinfunction "+IN_3") (pintype "input"))
      (node (ref "IC7") (pin "1") (pinfunction "AISEN_1") (pintype "bidirectional"))
      (node (ref "R21") (pin "1") (pinfunction "1_1") (pintype "passive"))
    )
    (net (code "24") (name "MOTOR_A_OUT1") (class "Default")
      (node (ref "C24") (pin "1") (pinfunction "1_1") (pintype "passive"))
      (node (ref "IC7") (pin "16") (pinfunction "AOUT1_16") (pintype "bidirectional"))
      (node (ref "R12") (pin "1") (pinfunction "1_1") (pintype "passive"))
    )
    (net (code "25") (name "MOTOR_A_OUT2") (class "Default")
      (node (ref "C24") (pin "2") (pinfunction "2_2") (pintype "passive"))
      (node (ref "IC7") (pin "2") (pinfunction "AOUT2_2") (pintype "bidirectional"))
      (node (ref "R13") (pin "1") (pinfunction "1_1") (pintype "passive"))
    )
    (net (code "26") (name "MOTOR_B_BEMF") (class "Default")
      (node (ref "C42") (pin "1") (pinfunction "1_1") (pintype "passive"))
      (node (ref "JMP_4") (pin "3") (pinfunction "3_3") (pintype "passive"))
      (node (ref "JMP_4") (pin "4") (pinfunction "4_4") (pintype "passive"))
      (node (ref "JMP_5") (pin "1") (pinfunction "1_1") (pintype "passive"))
      (node (ref "JMP_5") (pin "2") (pinfunction "2_2") (pintype "passive"))
      (node (ref "R31") (pin "2") (pinfunction "2_2") (pintype "passive"))
      (node (ref "U$20") (pin "14") (pinfunction "PTB2_14") (pintype "bidirectional"))
    )
    (net (code "27") (name "MOTOR_B_CURR") (class "Default")
      (node (ref "C44") (pin "1") (pinfunction "1_1") (pintype "passive"))
      (node (ref "JMP_17") (pin "1") (pinfunction "1_1") (pintype "passive"))
      (node (ref "JMP_17") (pin "2") (pinfunction "2_2") (pintype "passive"))
      (node (ref "R33") (pin "2") (pinfunction "2_2") (pintype "passive"))
      (node (ref "U$20") (pin "16") (pinfunction "PTA9_16") (pintype "bidirectional"))
    )
    (net (code "28") (name "MOTOR_B_IN1") (class "Default")
      (node (ref "IC7") (pin "7") (pinfunction "BIN1_7") (pintype "bidirectional"))
      (node (ref "U$20") (pin "1") (pinfunction "PTB6_1") (pintype "bidirectional"))
      (node (ref "U$27") (pin "D6") (pinfunction "*D6_D6") (pintype "bidirectional"))
    )
    (net (code "29") (name "MOTOR_B_IN2") (class "Default")
      (node (ref "IC7") (pin "8") (pinfunction "BIN2_8") (pintype "bidirectional"))
      (node (ref "JMP_12") (pin "3") (pinfunction "3_3") (pintype "passive"))
      (node (ref "JMP_12") (pin "4") (pinfunction "4_4") (pintype "passive"))
      (node (ref "JMP_13") (pin "1") (pinfunction "1_1") (pintype "passive"))
      (node (ref "JMP_13") (pin "2") (pinfunction "2_2") (pintype "passive"))
      (node (ref "U$20") (pin "2") (pinfunction "PTB7_2") (pintype "bidirectional"))
    )
    (net (code "30") (name "MOTOR_B_ISEN") (class "Default")
      (node (ref "IC6") (pin "5") (pinfunction "+IN_5") (pintype "input"))
      (node (ref "IC7") (pin "4") (pinfunction "BISEN_4") (pintype "bidirectional"))
      (node (ref "R23") (pin "1") (pinfunction "1_1") (pintype "passive"))
    )
    (net (code "31") (name "MOTOR_B_OUT1") (class "Default")
      (node (ref "C25") (pin "1") (pinfunction "1_1") (pintype "passive"))
      (node (ref "IC7") (pin "5") (pinfunction "BOUT1_5") (pintype "bidirectional"))
      (node (ref "R16") (pin "1") (pinfunction "1_1") (pintype "passive"))
    )
    (net (code "32") (name "MOTOR_B_OUT2") (class "Default")
      (node (ref "C25") (pin "2") (pinfunction "2_2") (pintype "passive"))
      (node (ref "IC7") (pin "3") (pinfunction "BOUT2_3") (pintype "bidirectional"))
      (node (ref "R17") (pin "1") (pinfunction "1_1") (pintype "passive"))
    )
    (net (code "33") (name "Net-(IC6A--IN)") (class "Default")
      (node (ref "IC6") (pin "2") (pinfunction "-IN_2") (pintype "input"))
      (node (ref "R20") (pin "2") (pinfunction "2_2") (pintype "passive"))
      (node (ref "R22") (pin "1") (pinfunction "1_1") (pintype "passive"))
    )
    (net (code "34") (name "Net-(IC6A-OUT)") (class "Default")
      (node (ref "IC6") (pin "1") (pinfunction "OUT_1") (pintype "output"))
      (node (ref "R22") (pin "2") (pinfunction "2_2") (pintype "passive"))
      (node (ref "R32") (pin "1") (pinfunction "1_1") (pintype "passive"))
    )
    (net (code "35") (name "Net-(IC6B--IN)") (class "Default")
      (node (ref "IC6") (pin "6") (pinfunction "-IN_6") (pintype "input"))
      (node (ref "R24") (pin "2") (pinfunction "2_2") (pintype "passive"))
      (node (ref "R26") (pin "1") (pinfunction "1_1") (pintype "passive"))
    )
    (net (code "36") (name "Net-(IC6B-OUT)") (class "Default")
      (node (ref "IC6") (pin "7") (pinfunction "OUT_7") (pintype "output"))
      (node (ref "R26") (pin "2") (pinfunction "2_2") (pintype "passive"))
      (node (ref "R33") (pin "1") (pinfunction "1_1") (pintype "passive"))
    )
    (net (code "37") (name "Net-(IC6C-+IN)") (class "Default")
      (node (ref "IC6") (pin "12") (pinfunction "+IN_12") (pintype "input"))
      (node (ref "R17") (pin "2") (pinfunction "2_2") (pintype "passive"))
      (node (ref "R19") (pin "2") (pinfunction "2_2") (pintype "passive"))
    )
    (net (code "38") (name "Net-(IC6C--IN)") (class "Default")
      (node (ref "IC6") (pin "11") (pinfunction "-IN_11") (pintype "input"))
      (node (ref "R16") (pin "2") (pinfunction "2_2") (pintype "passive"))
      (node (ref "R18") (pin "1") (pinfunction "1_1") (pintype "passive"))
    )
    (net (code "39") (name "Net-(IC6C-OUT)") (class "Default")
      (node (ref "IC6") (pin "10") (pinfunction "OUT_10") (pintype "output"))
      (node (ref "R18") (pin "2") (pinfunction "2_2") (pintype "passive"))
      (node (ref "R31") (pin "1") (pinfunction "1_1") (pintype "passive"))
    )
    (net (code "40") (name "Net-(IC6D-+IN)") (class "Default")
      (node (ref "IC6") (pin "14") (pinfunction "+IN_14") (pintype "input"))
      (node (ref "R13") (pin "2") (pinfunction "2_2") (pintype "passive"))
      (node (ref "R15") (pin "2") (pinfunction "2_2") (pintype "passive"))
    )
    (net (code "41") (name "Net-(IC6D--IN)") (class "Default")
      (node (ref "IC6") (pin "15") (pinfunction "-IN_15") (pintype "input"))
      (node (ref "R12") (pin "2") (pinfunction "2_2") (pintype "passive"))
      (node (ref "R14") (pin "1") (pinfunction "1_1") (pintype "passive"))
    )
    (net (code "42") (name "Net-(IC6D-OUT)") (class "Default")
      (node (ref "IC6") (pin "16") (pinfunction "OUT_16") (pintype "output"))
      (node (ref "R14") (pin "2") (pinfunction "2_2") (pintype "passive"))
      (node (ref "R30") (pin "1") (pinfunction "1_1") (pintype "passive"))
    )
    (net (code "43") (name "Net-(IC7A-V+)") (class "Default")
      (node (ref "C31") (pin "2") (pinfunction "2_2") (pintype "passive"))
      (node (ref "IC7") (pin "9") (pinfunction "V+_9") (pintype "power_in"))
    )
    (net (code "44") (name "Net-(IC7B-V-)") (class "Default")
      (node (ref "C32") (pin "1") (pinfunction "1_1") (pintype "passive"))
      (node (ref "IC7") (pin "12") (pinfunction "V-_12") (pintype "power_in"))
    )
    (net (code "45") (name "Net-(PWR_BATT-2)") (class "Default")
      (node (ref "PWR_BATT") (pin "V+") (pinfunction "2_V+") (pintype "passive"))
      (node (ref "PWR_SWITCH") (pin "2") (pinfunction "P_2") (pintype "passive"))
      (node (ref "PWR_SWITCH") (pin "5") (pinfunction "P_5") (pintype "passive"))
    )
    (net (code "46") (name "Net-(PWR_LED1-PadA)") (class "Default")
      (node (ref "PWR_LED1") (pin "A") (pinfunction "A_A") (pintype "passive"))
      (node (ref "R36") (pin "2") (pinfunction "2_2") (pintype "passive"))
    )
    (net (code "47") (name "Net-(R25-Pad1)") (class "Default")
      (node (ref "R25") (pin "1") (pinfunction "1_1") (pintype "passive"))
      (node (ref "STATUS_LED") (pin "A") (pinfunction "A_A") (pintype "passive"))
    )
    (net (code "48") (name "Net-(R40-Pad1)") (class "Default")
      (node (ref "R40") (pin "1") (pinfunction "1_1") (pintype "passive"))
      (node (ref "SPI") (pin "2") (pinfunction "2_2") (pintype "passive"))
    )
    (net (code "49") (name "Net-(R41-Pad1)") (class "Default")
      (node (ref "R41") (pin "1") (pinfunction "1_1") (pintype "passive"))
      (node (ref "SPI") (pin "3") (pinfunction "3_3") (pintype "passive"))
    )
    (net (code "50") (name "Net-(R42-Pad1)") (class "Default")
      (node (ref "R42") (pin "1") (pinfunction "1_1") (pintype "passive"))
      (node (ref "SPI") (pin "4") (pinfunction "4_4") (pintype "passive"))
    )
    (net (code "51") (name "Net-(U$1C-FB)") (class "Default")
      (node (ref "R4") (pin "1") (pinfunction "1_1") (pintype "passive"))
      (node (ref "R5") (pin "2") (pinfunction "2_2") (pintype "passive"))
      (node (ref "U$1") (pin "4") (pinfunction "FB_4") (pintype "bidirectional"))
    )
    (net (code "52") (name "Net-(U$1D-FB)") (class "Default")
      (node (ref "R2") (pin "1") (pinfunction "1_1") (pintype "passive"))
      (node (ref "R3") (pin "2") (pinfunction "2_2") (pintype "passive"))
      (node (ref "U$1") (pin "8") (pinfunction "FB_8") (pintype "bidirectional"))
    )
    (net (code "53") (name "Net-(U$2-PROG)") (class "Default")
      (node (ref "R7") (pin "2") (pinfunction "2_2") (pintype "passive"))
      (node (ref "U$2") (pin "5") (pinfunction "PROG_5") (pintype "bidirectional"))
    )
    (net (code "54") (name "Net-(U$11B-OUT)") (class "Default")
      (node (ref "R28") (pin "2") (pinfunction "2_2") (pintype "passive"))
      (node (ref "U$11") (pin "6") (pinfunction "OUT_6") (pintype "output"))
    )
    (net (code "55") (name "RESET") (class "Default")
      (node (ref "R38") (pin "1") (pinfunction "1_1") (pintype "passive"))
      (node (ref "U$20") (pin "23") (pinfunction "PTA1_23") (pintype "bidirectional"))
      (node (ref "U$27") (pin "RES") (pinfunction "RES_RES") (pintype "bidirectional"))
    )
    (net (code "56") (name "SENSE_I_BATT") (class "Default")
      (node (ref "C9") (pin "1") (pinfunction "1_1") (pintype "passive"))
      (node (ref "JMP_8") (pin "3") (pinfunction "3_3") (pintype "passive"))
      (node (ref "JMP_8") (pin "4") (pinfunction "4_4") (pintype "passive"))
      (node (ref "JMP_9") (pin "1") (pinfunction "1_1") (pintype "passive"))
      (node (ref "JMP_9") (pin "2") (pinfunction "2_2") (pintype "passive"))
      (node (ref "R28") (pin "1") (pinfunction "1_1") (pintype "passive"))
      (node (ref "R29") (pin "2") (pinfunction "2_2") (pintype "passive"))
      (node (ref "U$20") (pin "20") (pinfunction "PTA12_20") (pintype "bidirectional"))
    )
    (net (code "57") (name "SENSE_V_BATT") (class "Default")
      (node (ref "C3") (pin "1") (pinfunction "1_1") (pintype "passive"))
      (node (ref "JMP_6") (pin "3") (pinfunction "3_3") (pintype "passive"))
      (node (ref "JMP_6") (pin "4") (pinfunction "4_4") (pintype "passive"))
      (node (ref "JMP_7") (pin "1") (pinfunction "1_1") (pintype "passive"))
      (node (ref "JMP_7") (pin "2") (pinfunction "2_2") (pintype "passive"))
      (node (ref "R8") (pin "1") (pinfunction "1_1") (pintype "passive"))
      (node (ref "R9") (pin "2") (pinfunction "2_2") (pintype "passive"))
      (node (ref "U$20") (pin "19") (pinfunction "PTB5_19") (pintype "bidirectional"))
    )
    (net (code "58") (name "SENSE_V_BUS") (class "Default")
      (node (ref "C4") (pin "1") (pinfunction "1_1") (pintype "passive"))
      (node (ref "R10") (pin "1") (pinfunction "1_1") (pintype "passive"))
      (node (ref "R11") (pin "2") (pinfunction "2_2") (pintype "passive"))
      (node (ref "U$20") (pin "21") (pinfunction "PTB13_21") (pintype "bidirectional"))
      (node (ref "U$27") (pin "A5") (pinfunction "A5_A5") (pintype "bidirectional"))
    )
    (net (code "59") (name "SPI_MISO") (class "Default")
      (node (ref "R42") (pin "2") (pinfunction "2_2") (pintype "passive"))
      (node (ref "U$20") (pin "8") (pinfunction "PTA6_8") (pintype "bidirectional"))
      (node (ref "U$27") (pin "D12") (pinfunction "D12_D12") (pintype "bidirectional"))
    )
    (net (code "60") (name "SPI_MOSI") (class "Default")
      (node (ref "R41") (pin "2") (pinfunction "2_2") (pintype "passive"))
      (node (ref "U$20") (pin "11") (pinfunction "PTA7_11") (pintype "bidirectional"))
      (node (ref "U$27") (pin "D11") (pinfunction "*D11_D11") (pintype "bidirectional"))
    )
    (net (code "61") (name "SPI_SCK") (class "Default")
      (node (ref "R40") (pin "2") (pinfunction "2_2") (pintype "passive"))
      (node (ref "U$20") (pin "12") (pinfunction "PTB0_12") (pintype "bidirectional"))
      (node (ref "U$27") (pin "D13") (pinfunction "D13_D13") (pintype "bidirectional"))
    )
    (net (code "62") (name "SPI_SS") (class "Default")
      (node (ref "R35") (pin "1") (pinfunction "1_1") (pintype "passive"))
      (node (ref "SPI") (pin "1") (pinfunction "1_1") (pintype "passive"))
      (node (ref "U$20") (pin "7") (pinfunction "PTA5_7") (pintype "bidirectional"))
      (node (ref "U$27") (pin "D10") (pinfunction "*D10_D10") (pintype "bidirectional"))
    )
    (net (code "63") (name "SWD_CLK") (class "Default")
      (node (ref "R37") (pin "1") (pinfunction "1_1") (pintype "passive"))
      (node (ref "U$20") (pin "22") (pinfunction "PTA0_22") (pintype "bidirectional"))
      (node (ref "U$27") (pin "A3") (pinfunction "A3_A3") (pintype "bidirectional"))
    )
    (net (code "64") (name "SWD_DIO{slash}STATUS") (class "Default")
      (node (ref "JMP_10") (pin "3") (pinfunction "3_3") (pintype "passive"))
      (node (ref "JMP_10") (pin "4") (pinfunction "4_4") (pintype "passive"))
      (node (ref "JMP_11") (pin "1") (pinfunction "1_1") (pintype "passive"))
      (node (ref "JMP_11") (pin "2") (pinfunction "2_2") (pintype "passive"))
      (node (ref "R39") (pin "1") (pinfunction "1_1") (pintype "passive"))
      (node (ref "STATUS_LED") (pin "C") (pinfunction "C_C") (pintype "passive"))
      (node (ref "U$20") (pin "24") (pinfunction "PTA2_24") (pintype "bidirectional"))
    )
    (net (code "65") (name "V_1.5") (class "Default")
      (node (ref "C11") (pin "2") (pinfunction "2_2") (pintype "passive"))
      (node (ref "C6") (pin "1") (pinfunction "1_1") (pintype "passive"))
      (node (ref "R15") (pin "1") (pinfunction "1_1") (pintype "passive"))
      (node (ref "R19") (pin "1") (pinfunction "1_1") (pintype "passive"))
      (node (ref "R2") (pin "2") (pinfunction "2_2") (pintype "passive"))
      (node (ref "U$1") (pin "1") (pinfunction "OUT_1") (pintype "bidirectional"))
      (node (ref "U$11") (pin "1") (pinfunction "REF_1") (pintype "bidirectional"))
    )
    (net (code "66") (name "V_3.0") (class "Default")
      (node (ref "C10") (pin "1") (pinfunction "1_1") (pintype "passive"))
      (node (ref "C2") (pin "1") (pinfunction "1_1") (pintype "passive"))
      (node (ref "C29") (pin "1") (pinfunction "1_1") (pintype "passive"))
      (node (ref "C5") (pin "1") (pinfunction "1_1") (pintype "passive"))
      (node (ref "IC6") (pin "4") (pinfunction "V+_4") (pintype "power_in"))
      (node (ref "JMP_1") (pin "3") (pinfunction "3_3") (pintype "passive"))
      (node (ref "JMP_1") (pin "4") (pinfunction "4_4") (pintype "passive"))
      (node (ref "R25") (pin "2") (pinfunction "2_2") (pintype "passive"))
      (node (ref "R27") (pin "2") (pinfunction "2_2") (pintype "passive"))
      (node (ref "R34") (pin "2") (pinfunction "2_2") (pintype "passive"))
      (node (ref "R35") (pin "2") (pinfunction "2_2") (pintype "passive"))
      (node (ref "R36") (pin "1") (pinfunction "1_1") (pintype "passive"))
      (node (ref "R37") (pin "2") (pinfunction "2_2") (pintype "passive"))
      (node (ref "R38") (pin "2") (pinfunction "2_2") (pintype "passive"))
      (node (ref "R39") (pin "2") (pinfunction "2_2") (pintype "passive"))
      (node (ref "R4") (pin "2") (pinfunction "2_2") (pintype "passive"))
      (node (ref "U$1") (pin "3") (pinfunction "OUT_3") (pintype "bidirectional"))
      (node (ref "U$11") (pin "3") (pinfunction "V+_3") (pintype "power_in"))
      (node (ref "U$20") (pin "3") (pinfunction "V+_3") (pintype "power_in"))
      (node (ref "U$30") (pin "1") (pinfunction "1_1") (pintype "passive"))
      (node (ref "U$30") (pin "5") (pinfunction "1_5") (pintype "passive"))
    )
    (net (code "67") (name "V_BATT") (class "Default")
      (node (ref "C30") (pin "1") (pinfunction "1_1") (pintype "passive"))
      (node (ref "C31") (pin "1") (pinfunction "1_1") (pintype "passive"))
      (node (ref "C8") (pin "1") (pinfunction "1_1") (pintype "passive"))
      (node (ref "D1") (pin "A") (pinfunction "A_A") (pintype "passive"))
      (node (ref "IC7") (pin "10") (pinfunction "V+_10") (pintype "power_in"))
      (node (ref "IC7") (pin "15") (pinfunction "~{SLEEP}_15") (pintype "bidirectional"))
      (node (ref "R1") (pin "2") (pinfunction "2_2") (pintype "passive"))
      (node (ref "U$11") (pin "5") (pinfunction "-IN_5") (pintype "input"))
      (node (ref "U$2") (pin "3") (pinfunction "VBAT_3") (pintype "bidirectional"))
    )
    (net (code "68") (name "V_BUS") (class "Default")
      (node (ref "C1") (pin "1") (pinfunction "1_1") (pintype "passive"))
      (node (ref "C7") (pin "1") (pinfunction "1_1") (pintype "passive"))
      (node (ref "D1") (pin "C") (pinfunction "C_C") (pintype "passive"))
      (node (ref "JMP_0") (pin "3") (pinfunction "3_3") (pintype "passive"))
      (node (ref "JMP_0") (pin "4") (pinfunction "4_4") (pintype "passive"))
      (node (ref "PWR_BUS") (pin "2") (pinfunction "2_2") (pintype "passive"))
      (node (ref "R10") (pin "2") (pinfunction "2_2") (pintype "passive"))
      (node (ref "R6") (pin "1") (pinfunction "1_1") (pintype "passive"))
      (node (ref "U$1") (pin "2") (pinfunction "V+_2") (pintype "power_in"))
      (node (ref "U$1") (pin "6") (pinfunction "EN_6") (pintype "bidirectional"))
      (node (ref "U$2") (pin "4") (pinfunction "VDD_4") (pintype "bidirectional"))
    )
    (net (code "69") (name "unconnected-(IC7D-~{FAULT}-Pad6)") (class "Default")
      (node (ref "IC7") (pin "6") (pinfunction "~{FAULT}_6") (pintype "bidirectional"))
    )
    (net (code "70") (name "unconnected-(PWR_SWITCHA-S-Pad3)") (class "Default")
      (node (ref "PWR_SWITCH") (pin "3") (pinfunction "S_3") (pintype "passive"))
    )
    (net (code "71") (name "unconnected-(PWR_SWITCHB-S-Pad4)") (class "Default")
      (node (ref "PWR_SWITCH") (pin "4") (pinfunction "S_4") (pintype "passive"))
    )
    (net (code "72") (name "unconnected-(U$1A-PGOOD-Pad7)") (class "Default")
      (node (ref "U$1") (pin "7") (pinfunction "PGOOD_7") (pintype "bidirectional"))
    )
    (net (code "73") (name "unconnected-(U$27-Pad3.3V)") (class "Default")
      (node (ref "U$27") (pin "3.3V") (pinfunction "3.3V_3.3V") (pintype "bidirectional"))
    )
    (net (code "74") (name "unconnected-(U$27-PadIOREF)") (class "Default")
      (node (ref "U$27") (pin "IOREF") (pinfunction "IOREF_IOREF") (pintype "bidirectional"))
    )
    (net (code "75") (name "unconnected-(U$27-PadVIN)") (class "Default")
      (node (ref "U$27") (pin "VIN") (pinfunction "VIN_VIN") (pintype "bidirectional"))
    )
  )
)
